# FlashyStick.net
KiCad netlist of a schematic drawn in EAGLE
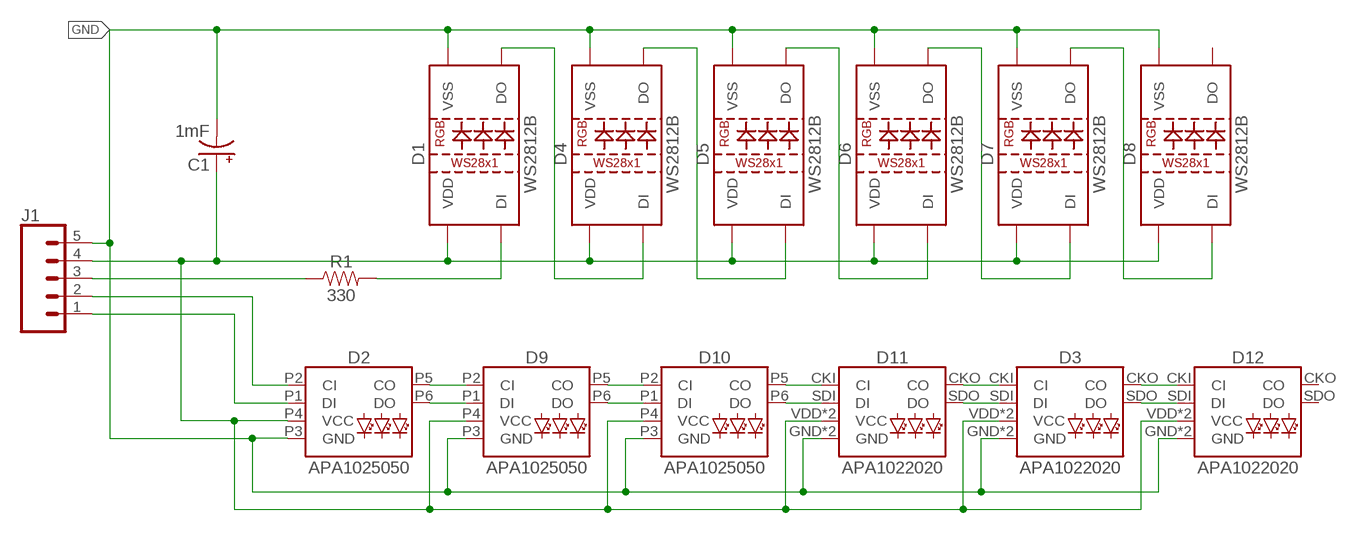
[diagram p0: schematic, sheet 1]

(export (version "E")
  (design (tool "Eeschema 10.0.6"))
  (components
    (comp (ref "C1")
      (value "1mF")
      (footprint "eagle-import:CPOL-RADIAL-5MM-10MM")
      (libsource (lib "eagle-import") (part "1000UF-RADIAL-5MM-25V-20%"))
    )
    (comp (ref "D1")
      (value "WS2812B")
      (footprint "eagle-import:WS2812B")
      (libsource (lib "eagle-import") (part "WS2812B"))
    )
    (comp (ref "D2")
      (value "APA1025050")
      (footprint "eagle-import:APA102-5050")
      (libsource (lib "eagle-import") (part "APA1025050"))
    )
    (comp (ref "D3")
      (value "APA1022020")
      (footprint "eagle-import:APA102-2020")
      (libsource (lib "eagle-import") (part "APA1022020"))
    )
    (comp (ref "D4")
      (value "WS2812B")
      (footprint "eagle-import:WS2812B")
      (libsource (lib "eagle-import") (part "WS2812B"))
    )
    (comp (ref "D5")
      (value "WS2812B")
      (footprint "eagle-import:WS2812B")
      (libsource (lib "eagle-import") (part "WS2812B"))
    )
    (comp (ref "D6")
      (value "WS2812B")
      (footprint "eagle-import:WS2812B")
      (libsource (lib "eagle-import") (part "WS2812B"))
    )
    (comp (ref "D7")
      (value "WS2812B")
      (footprint "eagle-import:WS2812B")
      (libsource (lib "eagle-import") (part "WS2812B"))
    )
    (comp (ref "D8")
      (value "WS2812B")
      (footprint "eagle-import:WS2812B")
      (libsource (lib "eagle-import") (part "WS2812B"))
    )
    (comp (ref "D9")
      (value "APA1025050")
      (footprint "eagle-import:APA102-5050")
      (libsource (lib "eagle-import") (part "APA1025050"))
    )
    (comp (ref "D10")
      (value "APA1025050")
      (footprint "eagle-import:APA102-5050")
      (libsource (lib "eagle-import") (part "APA1025050"))
    )
    (comp (ref "D11")
      (value "APA1022020")
      (footprint "eagle-import:APA102-2020")
      (libsource (lib "eagle-import") (part "APA1022020"))
    )
    (comp (ref "D12")
      (value "APA1022020")
      (footprint "eagle-import:APA102-2020")
      (libsource (lib "eagle-import") (part "APA1022020"))
    )
    (comp (ref "J1")
      (value "CONN_05")
      (footprint "eagle-import:1X05")
      (libsource (lib "eagle-import") (part "CONN_05"))
    )
    (comp (ref "R1")
      (value "330")
      (footprint "eagle-import:0603")
      (libsource (lib "eagle-import") (part "330OHM-0603-1/10W-1%"))
    )
  )
  (nets
    (net (code "1") (name "GND") (class "Default")
      (node (ref "C1") (pin "-") (pinfunction "-_-") (pintype "passive"))
      (node (ref "D1") (pin "3") (pinfunction "VSS_3") (pintype "bidirectional"))
      (node (ref "D10") (pin "P3") (pinfunction "GND_P3") (pintype "bidirectional"))
      (node (ref "D11") (pin "GND") (pinfunction "GND_GND") (pintype "bidirectional"))
      (node (ref "D11") (pin "GNDPAD") (pinfunction "GND_GNDPAD") (pintype "bidirectional"))
      (node (ref "D12") (pin "GND") (pinfunction "GND_GND") (pintype "bidirectional"))
      (node (ref "D12") (pin "GNDPAD") (pinfunction "GND_GNDPAD") (pintype "bidirectional"))
      (node (ref "D2") (pin "P3") (pinfunction "GND_P3") (pintype "bidirectional"))
      (node (ref "D3") (pin "GND") (pinfunction "GND_GND") (pintype "bidirectional"))
      (node (ref "D3") (pin "GNDPAD") (pinfunction "GND_GNDPAD") (pintype "bidirectional"))
      (node (ref "D4") (pin "3") (pinfunction "VSS_3") (pintype "bidirectional"))
      (node (ref "D5") (pin "3") (pinfunction "VSS_3") (pintype "bidirectional"))
      (node (ref "D6") (pin "3") (pinfunction "VSS_3") (pintype "bidirectional"))
      (node (ref "D7") (pin "3") (pinfunction "VSS_3") (pintype "bidirectional"))
      (node (ref "D8") (pin "3") (pinfunction "VSS_3") (pintype "bidirectional"))
      (node (ref "D9") (pin "P3") (pinfunction "GND_P3") (pintype "bidirectional"))
      (node (ref "J1") (pin "5") (pinfunction "5_5") (pintype "passive"))
    )
    (net (code "2") (name "Net-(D1-DI)") (class "Default")
      (node (ref "D1") (pin "4") (pinfunction "DI_4") (pintype "bidirectional"))
      (node (ref "R1") (pin "2") (pinfunction "2_2") (pintype "passive"))
    )
    (net (code "3") (name "Net-(D1-DO)") (class "Default")
      (node (ref "D1") (pin "2") (pinfunction "DO_2") (pintype "bidirectional"))
      (node (ref "D4") (pin "4") (pinfunction "DI_4") (pintype "bidirectional"))
    )
    (net (code "4") (name "Net-(D1-VDD)") (class "Default")
      (node (ref "C1") (pin "+") (pinfunction "+_+") (pintype "passive"))
      (node (ref "D1") (pin "1") (pinfunction "VDD_1") (pintype "bidirectional"))
      (node (ref "D10") (pin "P4") (pinfunction "VCC_P4") (pintype "bidirectional"))
      (node (ref "D11") (pin "VDD") (pinfunction "VCC_VDD") (pintype "bidirectional"))
      (node (ref "D11") (pin "VDDPAD") (pinfunction "VCC_VDDPAD") (pintype "bidirectional"))
      (node (ref "D12") (pin "VDD") (pinfunction "VCC_VDD") (pintype "bidirectional"))
      (node (ref "D12") (pin "VDDPAD") (pinfunction "VCC_VDDPAD") (pintype "bidirectional"))
      (node (ref "D2") (pin "P4") (pinfunction "VCC_P4") (pintype "bidirectional"))
      (node (ref "D3") (pin "VDD") (pinfunction "VCC_VDD") (pintype "bidirectional"))
      (node (ref "D3") (pin "VDDPAD") (pinfunction "VCC_VDDPAD") (pintype "bidirectional"))
      (node (ref "D4") (pin "1") (pinfunction "VDD_1") (pintype "bidirectional"))
      (node (ref "D5") (pin "1") (pinfunction "VDD_1") (pintype "bidirectional"))
      (node (ref "D6") (pin "1") (pinfunction "VDD_1") (pintype "bidirectional"))
      (node (ref "D7") (pin "1") (pinfunction "VDD_1") (pintype "bidirectional"))
      (node (ref "D8") (pin "1") (pinfunction "VDD_1") (pintype "bidirectional"))
      (node (ref "D9") (pin "P4") (pinfunction "VCC_P4") (pintype "bidirectional"))
      (node (ref "J1") (pin "4") (pinfunction "4_4") (pintype "passive"))
    )
    (net (code "5") (name "Net-(D2-CI)") (class "Default")
      (node (ref "D2") (pin "P2") (pinfunction "CI_P2") (pintype "bidirectional"))
      (node (ref "J1") (pin "2") (pinfunction "2_2") (pintype "passive"))
    )
    (net (code "6") (name "Net-(D2-CO)") (class "Default")
      (node (ref "D2") (pin "P5") (pinfunction "CO_P5") (pintype "bidirectional"))
      (node (ref "D9") (pin "P2") (pinfunction "CI_P2") (pintype "bidirectional"))
    )
    (net (code "7") (name "Net-(D2-DI)") (class "Default")
      (node (ref "D2") (pin "P1") (pinfunction "DI_P1") (pintype "bidirectional"))
      (node (ref "J1") (pin "1") (pinfunction "1_1") (pintype "passive"))
    )
    (net (code "8") (name "Net-(D2-DO)") (class "Default")
      (node (ref "D2") (pin "P6") (pinfunction "DO_P6") (pintype "bidirectional"))
      (node (ref "D9") (pin "P1") (pinfunction "DI_P1") (pintype "bidirectional"))
    )
    (net (code "9") (name "Net-(D4-DO)") (class "Default")
      (node (ref "D4") (pin "2") (pinfunction "DO_2") (pintype "bidirectional"))
      (node (ref "D5") (pin "4") (pinfunction "DI_4") (pintype "bidirectional"))
    )
    (net (code "10") (name "Net-(D5-DO)") (class "Default")
      (node (ref "D5") (pin "2") (pinfunction "DO_2") (pintype "bidirectional"))
      (node (ref "D6") (pin "4") (pinfunction "DI_4") (pintype "bidirectional"))
    )
    (net (code "11") (name "Net-(D6-DO)") (class "Default")
      (node (ref "D6") (pin "2") (pinfunction "DO_2") (pintype "bidirectional"))
      (node (ref "D7") (pin "4") (pinfunction "DI_4") (pintype "bidirectional"))
    )
    (net (code "12") (name "Net-(D7-DO)") (class "Default")
      (node (ref "D7") (pin "2") (pinfunction "DO_2") (pintype "bidirectional"))
      (node (ref "D8") (pin "4") (pinfunction "DI_4") (pintype "bidirectional"))
    )
    (net (code "13") (name "Net-(D10-CI)") (class "Default")
      (node (ref "D10") (pin "P2") (pinfunction "CI_P2") (pintype "bidirectional"))
      (node (ref "D9") (pin "P5") (pinfunction "CO_P5") (pintype "bidirectional"))
    )
    (net (code "14") (name "Net-(D10-CO)") (class "Default")
      (node (ref "D10") (pin "P5") (pinfunction "CO_P5") (pintype "bidirectional"))
      (node (ref "D11") (pin "CKI") (pinfunction "CI_CKI") (pintype "bidirectional"))
    )
    (net (code "15") (name "Net-(D10-DI)") (class "Default")
      (node (ref "D10") (pin "P1") (pinfunction "DI_P1") (pintype "bidirectional"))
      (node (ref "D9") (pin "P6") (pinfunction "DO_P6") (pintype "bidirectional"))
    )
    (net (code "16") (name "Net-(D10-DO)") (class "Default")
      (node (ref "D10") (pin "P6") (pinfunction "DO_P6") (pintype "bidirectional"))
      (node (ref "D11") (pin "SDI") (pinfunction "DI_SDI") (pintype "bidirectional"))
    )
    (net (code "17") (name "Net-(D11-CO)") (class "Default")
      (node (ref "D11") (pin "CKO") (pinfunction "CO_CKO") (pintype "bidirectional"))
      (node (ref "D3") (pin "CKI") (pinfunction "CI_CKI") (pintype "bidirectional"))
    )
    (net (code "18") (name "Net-(D11-DO)") (class "Default")
      (node (ref "D11") (pin "SDO") (pinfunction "DO_SDO") (pintype "bidirectional"))
      (node (ref "D3") (pin "SDI") (pinfunction "DI_SDI") (pintype "bidirectional"))
    )
    (net (code "19") (name "Net-(D12-CI)") (class "Default")
      (node (ref "D12") (pin "CKI") (pinfunction "CI_CKI") (pintype "bidirectional"))
      (node (ref "D3") (pin "CKO") (pinfunction "CO_CKO") (pintype "bidirectional"))
    )
    (net (code "20") (name "Net-(D12-DI)") (class "Default")
      (node (ref "D12") (pin "SDI") (pinfunction "DI_SDI") (pintype "bidirectional"))
      (node (ref "D3") (pin "SDO") (pinfunction "DO_SDO") (pintype "bidirectional"))
    )
    (net (code "21") (name "Net-(J1-Pad3)") (class "Default")
      (node (ref "J1") (pin "3") (pinfunction "3_3") (pintype "passive"))
      (node (ref "R1") (pin "1") (pinfunction "1_1") (pintype "passive"))
    )
    (net (code "22") (name "unconnected-(D8-DO-Pad2)") (class "Default")
      (node (ref "D8") (pin "2") (pinfunction "DO_2") (pintype "bidirectional"))
    )
    (net (code "23") (name "unconnected-(D12-CO-PadCKO)") (class "Default")
      (node (ref "D12") (pin "CKO") (pinfunction "CO_CKO") (pintype "bidirectional"))
    )
    (net (code "24") (name "unconnected-(D12-DO-PadSDO)") (class "Default")
      (node (ref "D12") (pin "SDO") (pinfunction "DO_SDO") (pintype "bidirectional"))
    )
  )
)
